# Stackduino-1_2.net
KiCad netlist of a schematic drawn in EAGLE
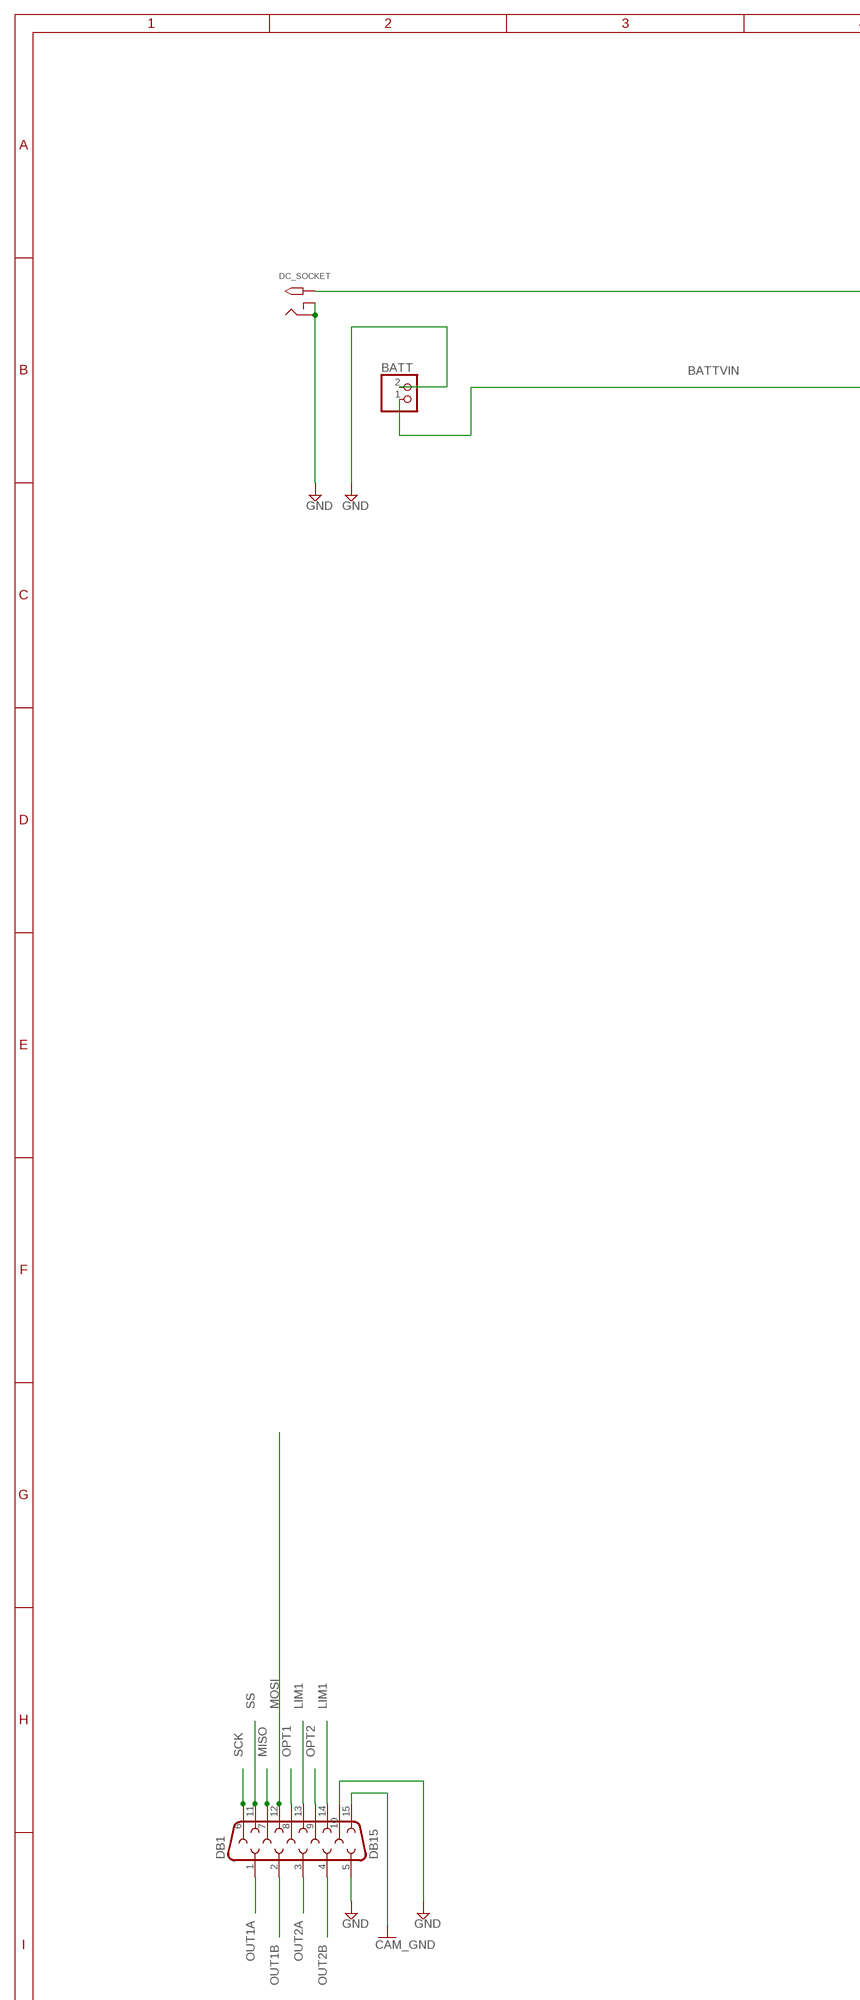
[diagram p0: schematic, sheet 1, part 1 of 2]
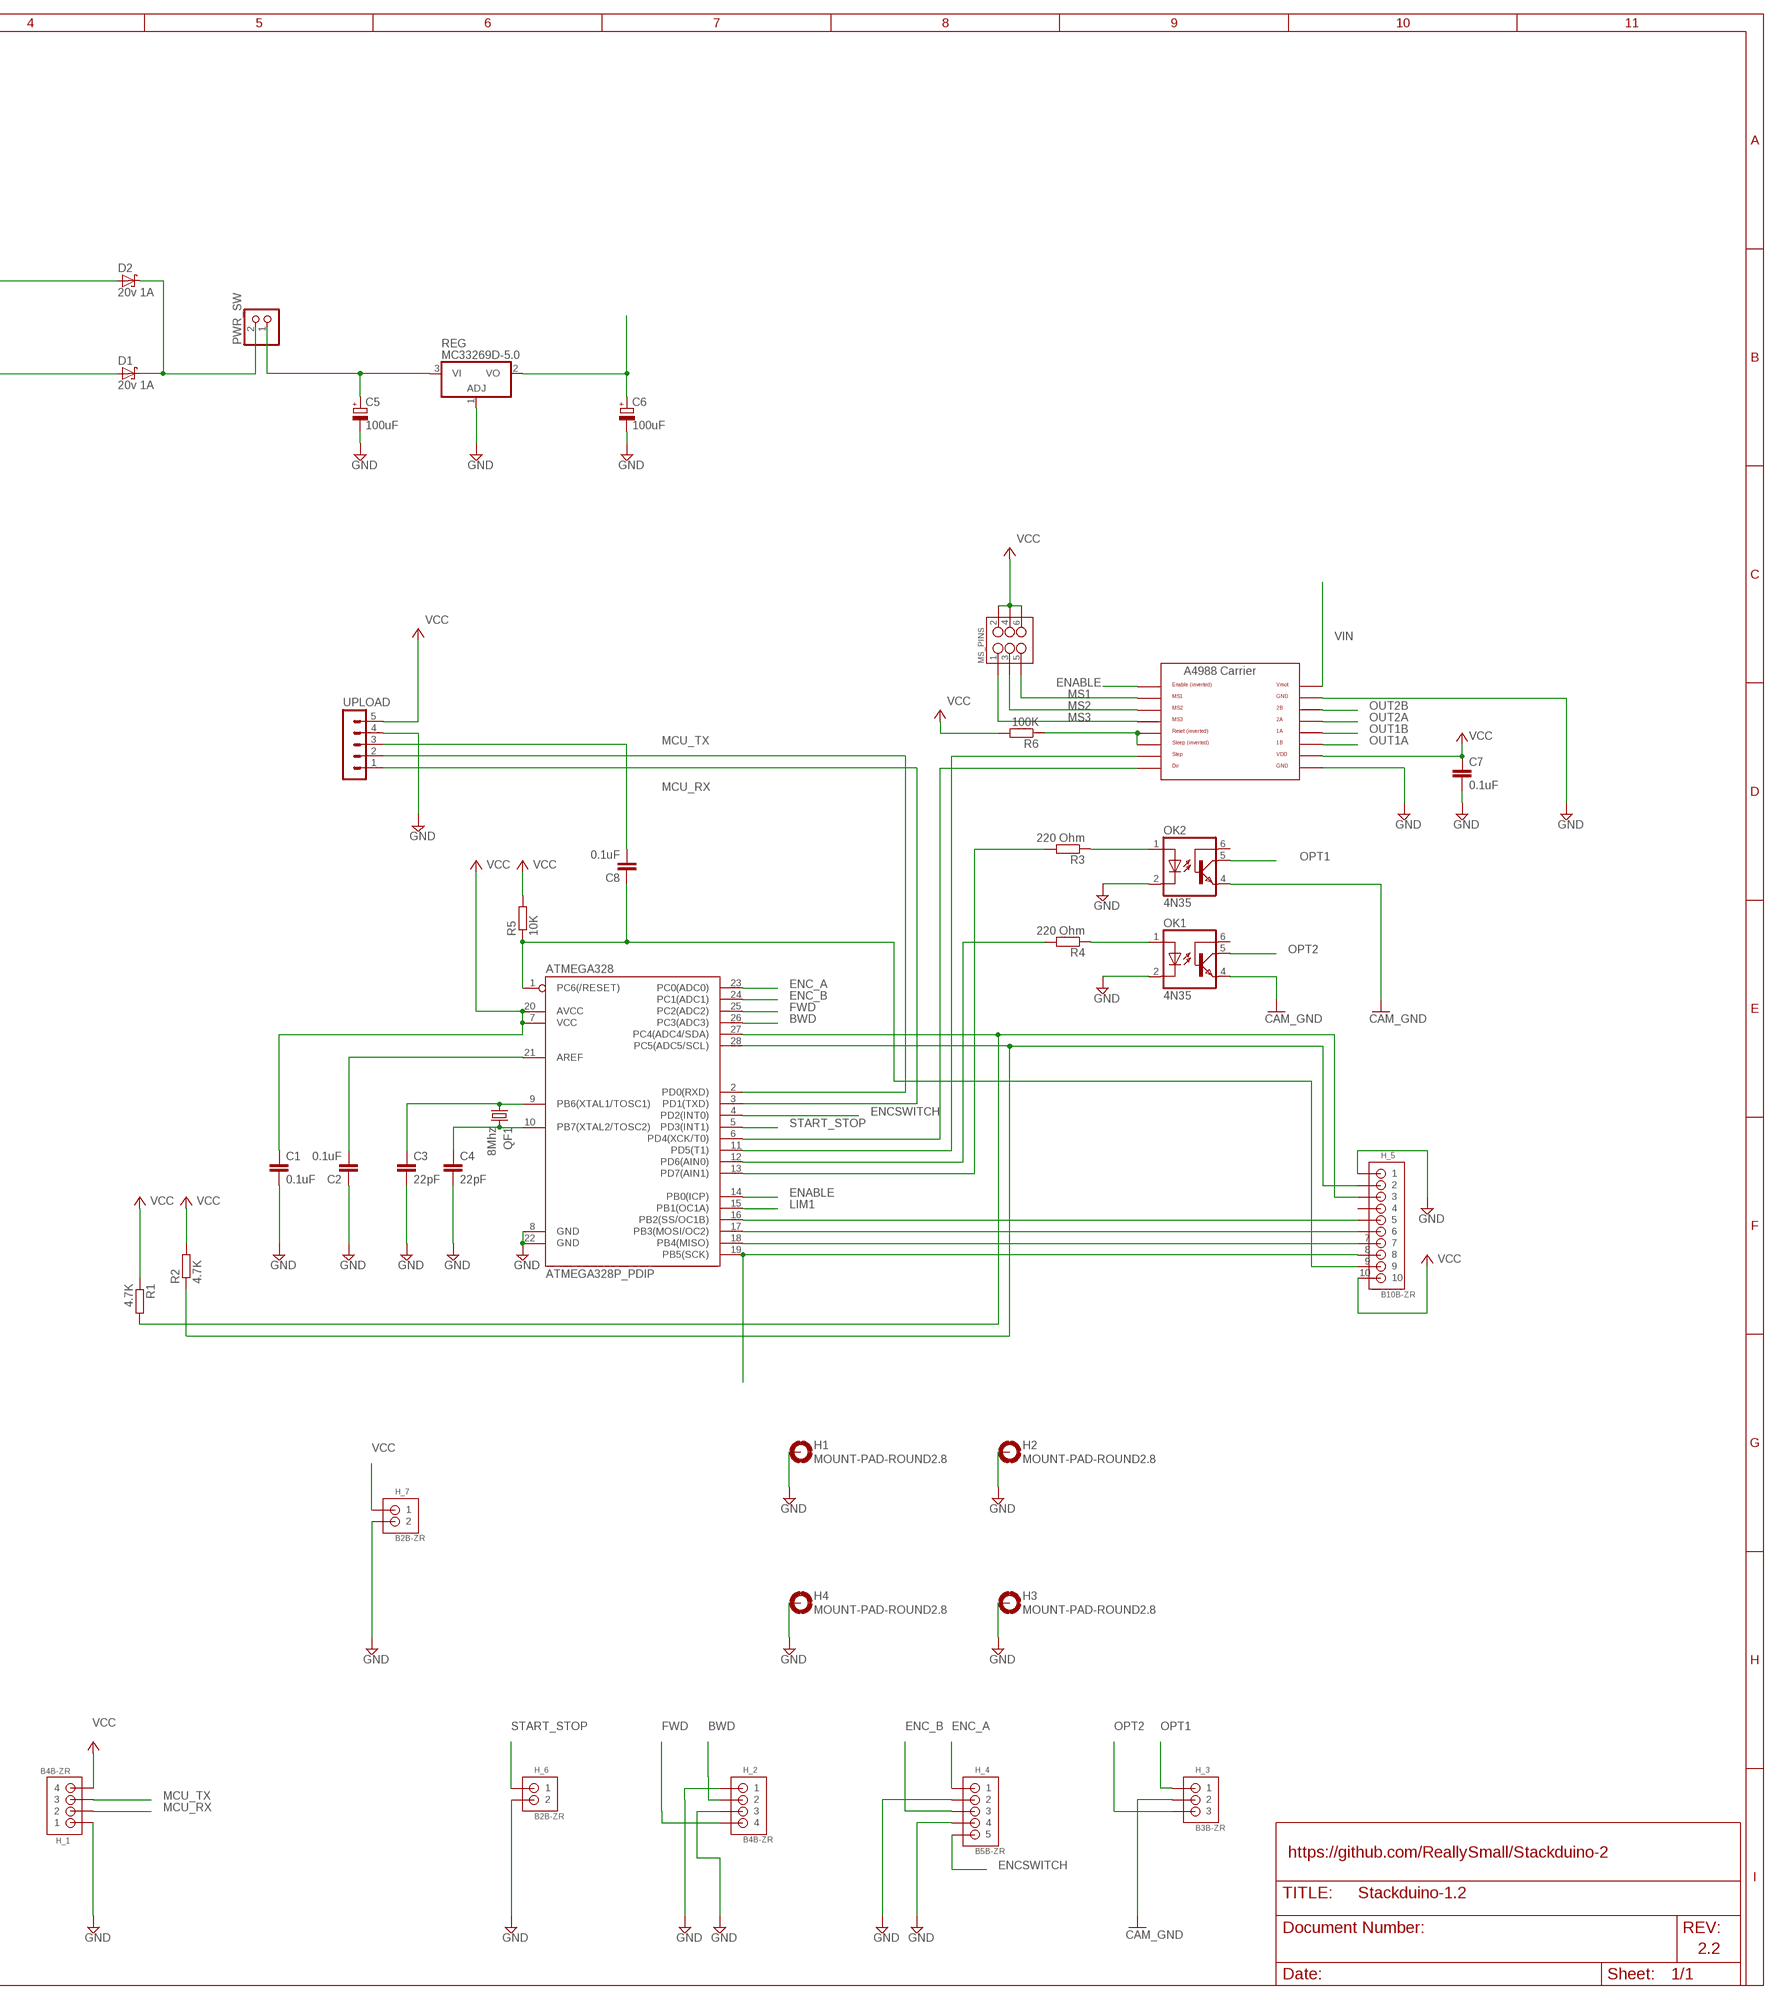
[diagram p1: schematic, sheet 1, part 2 of 2]

(export (version "E")
  (design (tool "Eeschema 10.0.6"))
  (components
    (comp (ref "A4988_CARRIER")
      (value "A4988BREAKOUT")
      (footprint "eagle-import:A4988BREAKOUT")
      (libsource (lib "eagle-import") (part "A4988BREAKOUT"))
    )
    (comp (ref "ATMEGA328")
      (value "ATMEGA328P_PDIP")
      (footprint "eagle-import:DIL28-3")
      (libsource (lib "eagle-import") (part "ATMEGA328P_PDIP"))
    )
    (comp (ref "BATT")
      (value "JST_2PIN-THM")
      (footprint "eagle-import:JST-PH-2-THM")
      (libsource (lib "eagle-import") (part "JST_2PIN-THM"))
    )
    (comp (ref "C1")
      (value "0.1uF")
      (footprint "eagle-import:C025-030X050")
      (libsource (lib "eagle-import") (part "C-EU025-030X050"))
    )
    (comp (ref "C2")
      (value "0.1uF")
      (footprint "eagle-import:C025-030X050")
      (libsource (lib "eagle-import") (part "C-EU025-030X050"))
    )
    (comp (ref "C3")
      (value "22pF")
      (footprint "eagle-import:C025-030X050")
      (libsource (lib "eagle-import") (part "C-EU025-030X050"))
    )
    (comp (ref "C4")
      (value "22pF")
      (footprint "eagle-import:C025-030X050")
      (libsource (lib "eagle-import") (part "C-EU025-030X050"))
    )
    (comp (ref "C5")
      (value "100uF")
      (footprint "eagle-import:E2,5-7")
      (libsource (lib "eagle-import") (part "CPOL-EUE2.5-7"))
    )
    (comp (ref "C6")
      (value "100uF")
      (footprint "eagle-import:E2,5-7")
      (libsource (lib "eagle-import") (part "CPOL-EUE2.5-7"))
    )
    (comp (ref "C7")
      (value "0.1uF")
      (footprint "eagle-import:C025-030X050")
      (libsource (lib "eagle-import") (part "C-EU025-030X050"))
    )
    (comp (ref "C8")
      (value "0.1uF")
      (footprint "eagle-import:C025-030X050")
      (libsource (lib "eagle-import") (part "C-EU025-030X050"))
    )
    (comp (ref "D1")
      (value "20v 1A")
      (footprint "eagle-import:DO41-10")
      (libsource (lib "eagle-import") (part "SCHOTTKY-DIODEDO41"))
    )
    (comp (ref "D2")
      (value "20v 1A")
      (footprint "eagle-import:DO41-10")
      (libsource (lib "eagle-import") (part "SCHOTTKY-DIODEDO41"))
    )
    (comp (ref "DB1")
      (value "DB15")
      (footprint "eagle-import:DB15")
      (libsource (lib "eagle-import") (part "DB15"))
    )
    (comp (ref "DC_SOCKET")
      (value "2.1MMJACKTHM")
      (footprint "eagle-import:PJ-102A")
      (libsource (lib "eagle-import") (part "2.1MMJACKTHM"))
    )
    (comp (ref "H1")
      (value "MOUNT-PAD-ROUND2.8")
      (footprint "eagle-import:2,8-PAD")
      (libsource (lib "eagle-import") (part "MOUNT-PAD-ROUND2.8"))
    )
    (comp (ref "H2")
      (value "MOUNT-PAD-ROUND2.8")
      (footprint "eagle-import:2,8-PAD")
      (libsource (lib "eagle-import") (part "MOUNT-PAD-ROUND2.8"))
    )
    (comp (ref "H3")
      (value "MOUNT-PAD-ROUND2.8")
      (footprint "eagle-import:2,8-PAD")
      (libsource (lib "eagle-import") (part "MOUNT-PAD-ROUND2.8"))
    )
    (comp (ref "H4")
      (value "MOUNT-PAD-ROUND2.8")
      (footprint "eagle-import:2,8-PAD")
      (libsource (lib "eagle-import") (part "MOUNT-PAD-ROUND2.8"))
    )
    (comp (ref "H_1")
      (value "B4B-ZR")
      (footprint "eagle-import:B4B-ZR")
      (libsource (lib "eagle-import") (part "B4B-ZR"))
    )
    (comp (ref "H_2")
      (value "B4B-ZR")
      (footprint "eagle-import:B4B-ZR")
      (libsource (lib "eagle-import") (part "B4B-ZR"))
    )
    (comp (ref "H_3")
      (value "B3B-ZR")
      (footprint "eagle-import:B3B-ZR")
      (libsource (lib "eagle-import") (part "B3B-ZR"))
    )
    (comp (ref "H_4")
      (value "B5B-ZR")
      (footprint "eagle-import:B5B-ZR")
      (libsource (lib "eagle-import") (part "B5B-ZR"))
    )
    (comp (ref "H_5")
      (value "B10B-ZR")
      (footprint "eagle-import:B10B-ZR")
      (libsource (lib "eagle-import") (part "B10B-ZR"))
    )
    (comp (ref "H_6")
      (value "B2B-ZR")
      (footprint "eagle-import:B2B-ZR")
      (libsource (lib "eagle-import") (part "B2B-ZR"))
    )
    (comp (ref "H_7")
      (value "B2B-ZR")
      (footprint "eagle-import:B2B-ZR")
      (libsource (lib "eagle-import") (part "B2B-ZR"))
    )
    (comp (ref "MS_PINS")
      (value "M03X22X3_SILK_MALE_PTH")
      (footprint "eagle-import:2X3")
      (libsource (lib "eagle-import") (part "M03X22X3_SILK_MALE_PTH"))
    )
    (comp (ref "OK1")
      (value "4N35")
      (footprint "eagle-import:DIL06")
      (fields (field (name "MF") "FAIRCHILD SEMICONDUCTOR"))
      (libsource (lib "eagle-import") (part "4N35"))
    )
    (comp (ref "OK2")
      (value "4N35")
      (footprint "eagle-import:DIL06")
      (fields (field (name "MF") "FAIRCHILD SEMICONDUCTOR"))
      (libsource (lib "eagle-import") (part "4N35"))
    )
    (comp (ref "PWR_SW")
      (value "JST_2PIN-THM")
      (footprint "eagle-import:JST-PH-2-THM")
      (libsource (lib "eagle-import") (part "JST_2PIN-THM"))
    )
    (comp (ref "QF1")
      (value "8Mhz")
      (footprint "eagle-import:HC49U-V")
      (libsource (lib "eagle-import") (part "CRYSTALHC49U-V"))
    )
    (comp (ref "R1")
      (value "4.7K")
      (footprint "eagle-import:0207_7")
      (libsource (lib "eagle-import") (part "R-EU_0207/7"))
    )
    (comp (ref "R2")
      (value "4.7K")
      (footprint "eagle-import:0207_7")
      (libsource (lib "eagle-import") (part "R-EU_0207/7"))
    )
    (comp (ref "R3")
      (value "220 Ohm")
      (footprint "eagle-import:0207_7")
      (libsource (lib "eagle-import") (part "R-EU_0207/7"))
    )
    (comp (ref "R4")
      (value "220 Ohm")
      (footprint "eagle-import:0207_7")
      (libsource (lib "eagle-import") (part "R-EU_0207/7"))
    )
    (comp (ref "R5")
      (value "10K")
      (footprint "eagle-import:0207_7")
      (libsource (lib "eagle-import") (part "R-EU_0207/7"))
    )
    (comp (ref "R6")
      (value "100K")
      (footprint "eagle-import:0207_7")
      (libsource (lib "eagle-import") (part "R-EU_0207/7"))
    )
    (comp (ref "REG")
      (value "MC33269D-5.0")
      (footprint "eagle-import:DPACK")
      (libsource (lib "eagle-import") (part "MC33269?D-5.0"))
    )
    (comp (ref "UPLOAD")
      (value "MA05-1")
      (footprint "eagle-import:MA05-1")
      (libsource (lib "eagle-import") (part "MA05-1"))
    )
  )
  (nets
    (net (code "1") (name "/BATTVIN") (class "Default")
      (node (ref "BATT") (pin "1") (pinfunction "2_1") (pintype "passive"))
      (node (ref "D1") (pin "A") (pinfunction "A_A") (pintype "passive"))
    )
    (net (code "2") (name "/BWD") (class "Default")
      (node (ref "ATMEGA328") (pin "26") (pinfunction "PC3(ADC3)_26") (pintype "bidirectional"))
      (node (ref "H_2") (pin "2") (pinfunction "2_2") (pintype "bidirectional"))
    )
    (net (code "3") (name "/ENABLE") (class "Default")
      (node (ref "A4988_CARRIER") (pin "EN") (pinfunction "EN_EN") (pintype "input"))
      (node (ref "ATMEGA328") (pin "14") (pinfunction "PB0(ICP)_14") (pintype "bidirectional"))
    )
    (net (code "4") (name "/ENCSWITCH") (class "Default")
      (node (ref "ATMEGA328") (pin "4") (pinfunction "PD2(INT0)_4") (pintype "bidirectional"))
      (node (ref "H_4") (pin "5") (pinfunction "5_5") (pintype "bidirectional"))
    )
    (net (code "5") (name "/ENC_A") (class "Default")
      (node (ref "ATMEGA328") (pin "23") (pinfunction "PC0(ADC0)_23") (pintype "bidirectional"))
      (node (ref "H_4") (pin "1") (pinfunction "1_1") (pintype "bidirectional"))
    )
    (net (code "6") (name "/ENC_B") (class "Default")
      (node (ref "ATMEGA328") (pin "24") (pinfunction "PC1(ADC1)_24") (pintype "bidirectional"))
      (node (ref "H_4") (pin "3") (pinfunction "3_3") (pintype "bidirectional"))
    )
    (net (code "7") (name "/FWD") (class "Default")
      (node (ref "ATMEGA328") (pin "25") (pinfunction "PC2(ADC2)_25") (pintype "bidirectional"))
      (node (ref "H_2") (pin "4") (pinfunction "4_4") (pintype "bidirectional"))
    )
    (net (code "8") (name "/LIM1") (class "Default")
      (node (ref "ATMEGA328") (pin "15") (pinfunction "PB1(OC1A)_15") (pintype "bidirectional"))
      (node (ref "DB1") (pin "13") (pinfunction "13_13") (pintype "passive"))
      (node (ref "DB1") (pin "14") (pinfunction "14_14") (pintype "passive"))
    )
    (net (code "9") (name "/MCU_RX") (class "Default")
      (node (ref "ATMEGA328") (pin "2") (pinfunction "PD0(RXD)_2") (pintype "bidirectional"))
      (node (ref "H_1") (pin "2") (pinfunction "2_2") (pintype "bidirectional"))
      (node (ref "UPLOAD") (pin "2") (pinfunction "2_2") (pintype "passive"))
    )
    (net (code "10") (name "/MCU_TX") (class "Default")
      (node (ref "ATMEGA328") (pin "3") (pinfunction "PD1(TXD)_3") (pintype "bidirectional"))
      (node (ref "H_1") (pin "3") (pinfunction "3_3") (pintype "bidirectional"))
      (node (ref "UPLOAD") (pin "1") (pinfunction "1_1") (pintype "passive"))
    )
    (net (code "11") (name "/MISO") (class "Default")
      (node (ref "ATMEGA328") (pin "18") (pinfunction "PB4(MISO)_18") (pintype "bidirectional"))
      (node (ref "DB1") (pin "7") (pinfunction "7_7") (pintype "passive"))
      (node (ref "H_5") (pin "7") (pinfunction "7_7") (pintype "bidirectional"))
    )
    (net (code "12") (name "/MOSI") (class "Default")
      (node (ref "ATMEGA328") (pin "17") (pinfunction "PB3(MOSI/OC2)_17") (pintype "bidirectional"))
      (node (ref "DB1") (pin "12") (pinfunction "12_12") (pintype "passive"))
      (node (ref "H_5") (pin "6") (pinfunction "6_6") (pintype "bidirectional"))
    )
    (net (code "13") (name "/MS1") (class "Default")
      (node (ref "A4988_CARRIER") (pin "MS1") (pinfunction "MS1_MS1") (pintype "input"))
      (node (ref "MS_PINS") (pin "5") (pinfunction "5_5") (pintype "bidirectional"))
    )
    (net (code "14") (name "/MS2") (class "Default")
      (node (ref "A4988_CARRIER") (pin "MS2") (pinfunction "MS2_MS2") (pintype "input"))
      (node (ref "MS_PINS") (pin "3") (pinfunction "3_3") (pintype "bidirectional"))
    )
    (net (code "15") (name "/MS3") (class "Default")
      (node (ref "A4988_CARRIER") (pin "MS3") (pinfunction "MS3_MS3") (pintype "input"))
      (node (ref "MS_PINS") (pin "1") (pinfunction "1_1") (pintype "bidirectional"))
    )
    (net (code "16") (name "/OPT1") (class "Default")
      (node (ref "DB1") (pin "8") (pinfunction "8_8") (pintype "passive"))
      (node (ref "H_3") (pin "1") (pinfunction "1_1") (pintype "bidirectional"))
      (node (ref "OK2") (pin "5") (pinfunction "COL_5") (pintype "passive"))
    )
    (net (code "17") (name "/OPT2") (class "Default")
      (node (ref "DB1") (pin "9") (pinfunction "9_9") (pintype "passive"))
      (node (ref "H_3") (pin "3") (pinfunction "3_3") (pintype "bidirectional"))
      (node (ref "OK1") (pin "5") (pinfunction "COL_5") (pintype "passive"))
    )
    (net (code "18") (name "/OUT1A") (class "Default")
      (node (ref "A4988_CARRIER") (pin "1B") (pinfunction "1B_1B") (pintype "output"))
      (node (ref "DB1") (pin "1") (pinfunction "1_1") (pintype "passive"))
    )
    (net (code "19") (name "/OUT1B") (class "Default")
      (node (ref "A4988_CARRIER") (pin "1A") (pinfunction "1A_1A") (pintype "output"))
      (node (ref "DB1") (pin "2") (pinfunction "2_2") (pintype "passive"))
    )
    (net (code "20") (name "/OUT2A") (class "Default")
      (node (ref "A4988_CARRIER") (pin "2A") (pinfunction "2A_2A") (pintype "output"))
      (node (ref "DB1") (pin "3") (pinfunction "3_3") (pintype "passive"))
    )
    (net (code "21") (name "/OUT2B") (class "Default")
      (node (ref "A4988_CARRIER") (pin "2B") (pinfunction "2B_2B") (pintype "output"))
      (node (ref "DB1") (pin "4") (pinfunction "4_4") (pintype "passive"))
    )
    (net (code "22") (name "/SCK") (class "Default")
      (node (ref "ATMEGA328") (pin "19") (pinfunction "PB5(SCK)_19") (pintype "bidirectional"))
      (node (ref "DB1") (pin "6") (pinfunction "6_6") (pintype "passive"))
      (node (ref "H_5") (pin "8") (pinfunction "8_8") (pintype "bidirectional"))
    )
    (net (code "23") (name "/SS") (class "Default")
      (node (ref "ATMEGA328") (pin "16") (pinfunction "PB2(SS/OC1B)_16") (pintype "bidirectional"))
      (node (ref "DB1") (pin "11") (pinfunction "11_11") (pintype "passive"))
      (node (ref "H_5") (pin "5") (pinfunction "5_5") (pintype "bidirectional"))
    )
    (net (code "24") (name "/START_STOP") (class "Default")
      (node (ref "ATMEGA328") (pin "5") (pinfunction "PD3(INT1)_5") (pintype "bidirectional"))
      (node (ref "H_6") (pin "1") (pinfunction "1_1") (pintype "bidirectional"))
    )
    (net (code "25") (name "/VIN") (class "Default")
      (node (ref "A4988_CARRIER") (pin "VMOT") (pinfunction "VMOT_VMOT") (pintype "power_in"))
      (node (ref "C5") (pin "+") (pinfunction "+_+") (pintype "passive"))
      (node (ref "PWR_SW") (pin "1") (pinfunction "2_1") (pintype "passive"))
      (node (ref "REG") (pin "3") (pinfunction "VI_3") (pintype "input"))
    )
    (net (code "26") (name "CAM_GND") (class "Default")
      (node (ref "DB1") (pin "15") (pinfunction "15_15") (pintype "passive"))
      (node (ref "H_3") (pin "2") (pinfunction "2_2") (pintype "bidirectional"))
      (node (ref "OK1") (pin "4") (pinfunction "EMI_4") (pintype "passive"))
      (node (ref "OK2") (pin "4") (pinfunction "EMI_4") (pintype "passive"))
    )
    (net (code "27") (name "GND") (class "Default")
      (node (ref "A4988_CARRIER") (pin "GND") (pinfunction "GND_GND") (pintype "power_in"))
      (node (ref "A4988_CARRIER") (pin "GND@0") (pinfunction "GND_GND@0") (pintype "power_in"))
      (node (ref "ATMEGA328") (pin "22") (pinfunction "GND_22") (pintype "bidirectional"))
      (node (ref "ATMEGA328") (pin "8") (pinfunction "GND_8") (pintype "bidirectional"))
      (node (ref "BATT") (pin "2") (pinfunction "1_2") (pintype "passive"))
      (node (ref "C1") (pin "2") (pinfunction "2_2") (pintype "passive"))
      (node (ref "C2") (pin "1") (pinfunction "1_1") (pintype "passive"))
      (node (ref "C3") (pin "2") (pinfunction "2_2") (pintype "passive"))
      (node (ref "C4") (pin "2") (pinfunction "2_2") (pintype "passive"))
      (node (ref "C5") (pin "-") (pinfunction "-_-") (pintype "passive"))
      (node (ref "C6") (pin "-") (pinfunction "-_-") (pintype "passive"))
      (node (ref "C7") (pin "2") (pinfunction "2_2") (pintype "passive"))
      (node (ref "DB1") (pin "10") (pinfunction "10_10") (pintype "passive"))
      (node (ref "DB1") (pin "5") (pinfunction "5_5") (pintype "passive"))
      (node (ref "DC_SOCKET") (pin "RING") (pinfunction "RING_RING") (pintype "bidirectional"))
      (node (ref "DC_SOCKET") (pin "RING_SW") (pinfunction "RING_SW_RING_SW") (pintype "bidirectional"))
      (node (ref "H1") (pin "B2,8") (pinfunction "MOUNT_B2,8") (pintype "passive"))
      (node (ref "H2") (pin "B2,8") (pinfunction "MOUNT_B2,8") (pintype "passive"))
      (node (ref "H3") (pin "B2,8") (pinfunction "MOUNT_B2,8") (pintype "passive"))
      (node (ref "H4") (pin "B2,8") (pinfunction "MOUNT_B2,8") (pintype "passive"))
      (node (ref "H_1") (pin "1") (pinfunction "1_1") (pintype "bidirectional"))
      (node (ref "H_2") (pin "1") (pinfunction "1_1") (pintype "bidirectional"))
      (node (ref "H_2") (pin "3") (pinfunction "3_3") (pintype "bidirectional"))
      (node (ref "H_4") (pin "2") (pinfunction "2_2") (pintype "bidirectional"))
      (node (ref "H_4") (pin "4") (pinfunction "4_4") (pintype "bidirectional"))
      (node (ref "H_5") (pin "1") (pinfunction "1_1") (pintype "bidirectional"))
      (node (ref "H_6") (pin "2") (pinfunction "2_2") (pintype "bidirectional"))
      (node (ref "H_7") (pin "2") (pinfunction "2_2") (pintype "bidirectional"))
      (node (ref "OK1") (pin "2") (pinfunction "C_2") (pintype "passive"))
      (node (ref "OK2") (pin "2") (pinfunction "C_2") (pintype "passive"))
      (node (ref "REG") (pin "1") (pinfunction "ADJ_1") (pintype "input"))
      (node (ref "UPLOAD") (pin "4") (pinfunction "4_4") (pintype "passive"))
    )
    (net (code "28") (name "Net-(A4988_CARRIER-SLEEP)") (class "Default")
      (node (ref "A4988_CARRIER") (pin "RST") (pinfunction "RST_RST") (pintype "input"))
      (node (ref "A4988_CARRIER") (pin "SLP") (pinfunction "SLEEP_SLP") (pintype "input"))
      (node (ref "R6") (pin "1") (pinfunction "1_1") (pintype "passive"))
    )
    (net (code "29") (name "Net-(ATMEGA328-AREF)") (class "Default")
      (node (ref "ATMEGA328") (pin "21") (pinfunction "AREF_21") (pintype "bidirectional"))
      (node (ref "C2") (pin "2") (pinfunction "2_2") (pintype "passive"))
    )
    (net (code "30") (name "Net-(ATMEGA328-PB6(XTAL1{slash}TOSC1))") (class "Default")
      (node (ref "ATMEGA328") (pin "9") (pinfunction "PB6(XTAL1/TOSC1)_9") (pintype "bidirectional"))
      (node (ref "C3") (pin "1") (pinfunction "1_1") (pintype "passive"))
      (node (ref "QF1") (pin "1") (pinfunction "1_1") (pintype "passive"))
    )
    (net (code "31") (name "Net-(ATMEGA328-PB7(XTAL2{slash}TOSC2))") (class "Default")
      (node (ref "ATMEGA328") (pin "10") (pinfunction "PB7(XTAL2/TOSC2)_10") (pintype "bidirectional"))
      (node (ref "C4") (pin "1") (pinfunction "1_1") (pintype "passive"))
      (node (ref "QF1") (pin "2") (pinfunction "2_2") (pintype "passive"))
    )
    (net (code "32") (name "Net-(ATMEGA328-PC4(ADC4{slash}SDA))") (class "Default")
      (node (ref "ATMEGA328") (pin "27") (pinfunction "PC4(ADC4/SDA)_27") (pintype "bidirectional"))
      (node (ref "H_5") (pin "3") (pinfunction "3_3") (pintype "bidirectional"))
      (node (ref "R1") (pin "2") (pinfunction "2_2") (pintype "passive"))
    )
    (net (code "33") (name "Net-(ATMEGA328-PC5(ADC5{slash}SCL))") (class "Default")
      (node (ref "ATMEGA328") (pin "28") (pinfunction "PC5(ADC5/SCL)_28") (pintype "bidirectional"))
      (node (ref "H_5") (pin "2") (pinfunction "2_2") (pintype "bidirectional"))
      (node (ref "R2") (pin "1") (pinfunction "1_1") (pintype "passive"))
    )
    (net (code "34") (name "Net-(ATMEGA328-PC6({slash}RESET))") (class "Default")
      (node (ref "ATMEGA328") (pin "1") (pinfunction "PC6(/RESET)_1") (pintype "bidirectional"))
      (node (ref "C8") (pin "1") (pinfunction "1_1") (pintype "passive"))
      (node (ref "H_5") (pin "9") (pinfunction "9_9") (pintype "bidirectional"))
      (node (ref "R5") (pin "1") (pinfunction "1_1") (pintype "passive"))
    )
    (net (code "35") (name "Net-(ATMEGA328-PD4(XCK{slash}T0))") (class "Default")
      (node (ref "A4988_CARRIER") (pin "DIR") (pinfunction "DIR_DIR") (pintype "input"))
      (node (ref "ATMEGA328") (pin "6") (pinfunction "PD4(XCK/T0)_6") (pintype "bidirectional"))
    )
    (net (code "36") (name "Net-(ATMEGA328-PD5(T1))") (class "Default")
      (node (ref "A4988_CARRIER") (pin "STEP") (pinfunction "STEP_STEP") (pintype "input"))
      (node (ref "ATMEGA328") (pin "11") (pinfunction "PD5(T1)_11") (pintype "bidirectional"))
    )
    (net (code "37") (name "Net-(ATMEGA328-PD6(AIN0))") (class "Default")
      (node (ref "ATMEGA328") (pin "12") (pinfunction "PD6(AIN0)_12") (pintype "bidirectional"))
      (node (ref "R4") (pin "2") (pinfunction "2_2") (pintype "passive"))
    )
    (net (code "38") (name "Net-(ATMEGA328-PD7(AIN1))") (class "Default")
      (node (ref "ATMEGA328") (pin "13") (pinfunction "PD7(AIN1)_13") (pintype "bidirectional"))
      (node (ref "R3") (pin "2") (pinfunction "2_2") (pintype "passive"))
    )
    (net (code "39") (name "Net-(C8-Pad2)") (class "Default")
      (node (ref "C8") (pin "2") (pinfunction "2_2") (pintype "passive"))
      (node (ref "UPLOAD") (pin "3") (pinfunction "3_3") (pintype "passive"))
    )
    (net (code "40") (name "Net-(D2-PadA)") (class "Default")
      (node (ref "D2") (pin "A") (pinfunction "A_A") (pintype "passive"))
      (node (ref "DC_SOCKET") (pin "TIP") (pinfunction "TIP_TIP") (pintype "bidirectional"))
    )
    (net (code "41") (name "Net-(OK1-A)") (class "Default")
      (node (ref "OK1") (pin "1") (pinfunction "A_1") (pintype "passive"))
      (node (ref "R4") (pin "1") (pinfunction "1_1") (pintype "passive"))
    )
    (net (code "42") (name "Net-(OK2-A)") (class "Default")
      (node (ref "OK2") (pin "1") (pinfunction "A_1") (pintype "passive"))
      (node (ref "R3") (pin "1") (pinfunction "1_1") (pintype "passive"))
    )
    (net (code "43") (name "Net-(PWR_SW-1)") (class "Default")
      (node (ref "D1") (pin "C") (pinfunction "C_C") (pintype "passive"))
      (node (ref "D2") (pin "C") (pinfunction "C_C") (pintype "passive"))
      (node (ref "PWR_SW") (pin "2") (pinfunction "1_2") (pintype "passive"))
    )
    (net (code "44") (name "VCC") (class "Default")
      (node (ref "A4988_CARRIER") (pin "VDD") (pinfunction "VDD_VDD") (pintype "power_in"))
      (node (ref "ATMEGA328") (pin "20") (pinfunction "AVCC_20") (pintype "bidirectional"))
      (node (ref "ATMEGA328") (pin "7") (pinfunction "VCC_7") (pintype "bidirectional"))
      (node (ref "C1") (pin "1") (pinfunction "1_1") (pintype "passive"))
      (node (ref "C6") (pin "+") (pinfunction "+_+") (pintype "passive"))
      (node (ref "C7") (pin "1") (pinfunction "1_1") (pintype "passive"))
      (node (ref "H_1") (pin "4") (pinfunction "4_4") (pintype "bidirectional"))
      (node (ref "H_5") (pin "10") (pinfunction "10_10") (pintype "bidirectional"))
      (node (ref "H_7") (pin "1") (pinfunction "1_1") (pintype "bidirectional"))
      (node (ref "MS_PINS") (pin "2") (pinfunction "2_2") (pintype "bidirectional"))
      (node (ref "MS_PINS") (pin "4") (pinfunction "4_4") (pintype "bidirectional"))
      (node (ref "MS_PINS") (pin "6") (pinfunction "6_6") (pintype "bidirectional"))
      (node (ref "R1") (pin "1") (pinfunction "1_1") (pintype "passive"))
      (node (ref "R2") (pin "2") (pinfunction "2_2") (pintype "passive"))
      (node (ref "R5") (pin "2") (pinfunction "2_2") (pintype "passive"))
      (node (ref "R6") (pin "2") (pinfunction "2_2") (pintype "passive"))
      (node (ref "REG") (pin "2") (pinfunction "VO_2") (pintype "passive"))
      (node (ref "UPLOAD") (pin "5") (pinfunction "5_5") (pintype "passive"))
    )
    (net (code "45") (name "unconnected-(H_5-Pad4)") (class "Default")
      (node (ref "H_5") (pin "4") (pinfunction "4_4") (pintype "bidirectional"))
    )
    (net (code "46") (name "unconnected-(OK1-BAS-Pad6)") (class "Default")
      (node (ref "OK1") (pin "6") (pinfunction "BAS_6") (pintype "passive"))
    )
    (net (code "47") (name "unconnected-(OK2-BAS-Pad6)") (class "Default")
      (node (ref "OK2") (pin "6") (pinfunction "BAS_6") (pintype "passive"))
    )
  )
)
